# ENCODER_V2.net
KiCad netlist of a schematic drawn in EAGLE
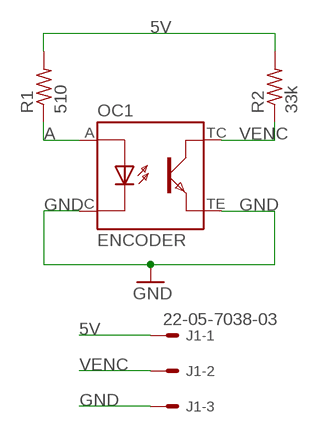
[diagram p0: schematic, sheet 1]

(export (version "E")
  (design (tool "Eeschema 10.0.6"))
  (components
    (comp (ref "J1")
      (value "22-05-7038-03")
      (footprint "eagle-import:7395-03")
      (fields (field (name "MF") "MOLEX"))
      (libsource (lib "eagle-import") (part "22-?-0305-7038"))
    )
    (comp (ref "OC1")
      (value "ENCODER")
      (footprint "eagle-import:PI_GP1S53VJ000F")
      (libsource (lib "eagle-import") (part "PC-GP1S53V"))
    )
    (comp (ref "R1")
      (value "510")
      (footprint "eagle-import:R0805")
      (libsource (lib "eagle-import") (part "R-US_R0805"))
    )
    (comp (ref "R2")
      (value "33k")
      (footprint "eagle-import:R0805")
      (libsource (lib "eagle-import") (part "R-US_R0805"))
    )
  )
  (nets
    (net (code "1") (name "/5V") (class "Default")
      (node (ref "J1") (pin "1") (pinfunction "S_1") (pintype "passive"))
      (node (ref "R1") (pin "2") (pinfunction "2_2") (pintype "passive"))
      (node (ref "R2") (pin "2") (pinfunction "2_2") (pintype "passive"))
    )
    (net (code "2") (name "/A") (class "Default")
      (node (ref "OC1") (pin "A") (pinfunction "A_A") (pintype "bidirectional"))
      (node (ref "R1") (pin "1") (pinfunction "1_1") (pintype "passive"))
    )
    (net (code "3") (name "/VENC") (class "Default")
      (node (ref "J1") (pin "2") (pinfunction "S_2") (pintype "passive"))
      (node (ref "OC1") (pin "TC") (pinfunction "TC_TC") (pintype "bidirectional"))
      (node (ref "R2") (pin "1") (pinfunction "1_1") (pintype "passive"))
    )
    (net (code "4") (name "GND") (class "Default")
      (node (ref "J1") (pin "3") (pinfunction "S_3") (pintype "passive"))
      (node (ref "OC1") (pin "C") (pinfunction "C_C") (pintype "bidirectional"))
      (node (ref "OC1") (pin "TE") (pinfunction "TE_TE") (pintype "bidirectional"))
    )
  )
)
